# SFPextension.net
KiCad netlist of a schematic drawn in Altium Designer
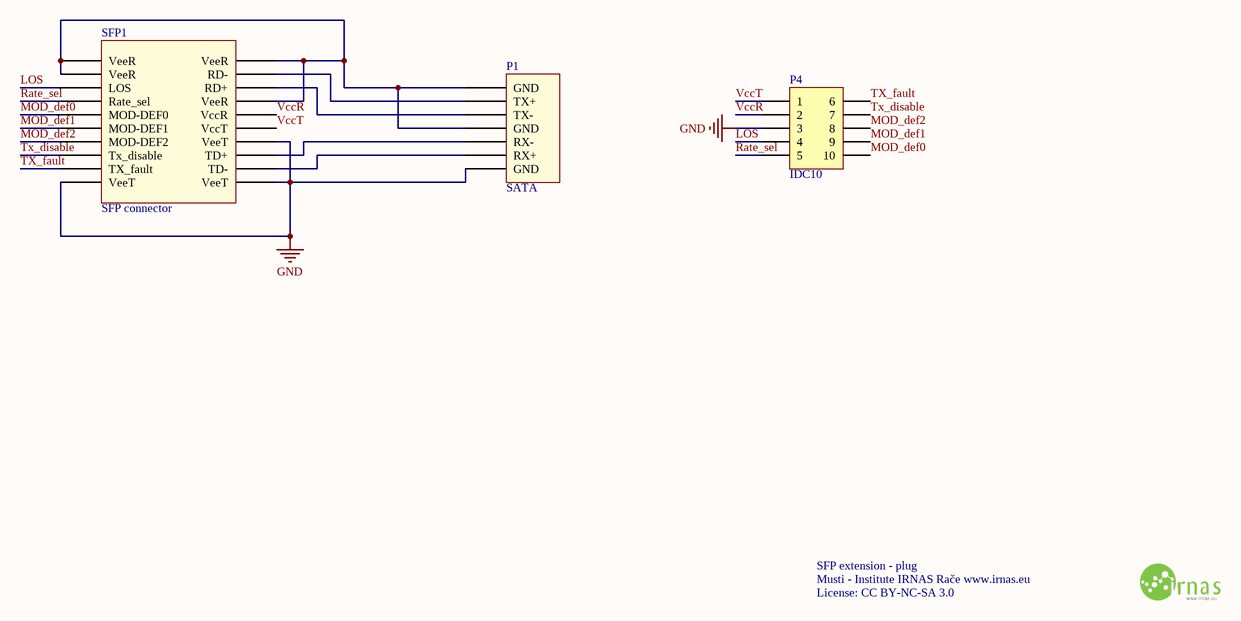
[diagram p0: SFPextension.SchDoc]

(export (version "E")
  (design (tool "Eeschema 10.0.6"))
  (components
    (comp (ref "P1")
      (value "SATA")
      (footprint "SATA pcb")
      (description "sata")
      (libsource (lib "GeneralComponents") (part "SATA"))
    )
    (comp (ref "P4")
      (value "IDC10")
      (footprint "HDR2X5_CEN")
      (description "Header, 5-Pin, Dual row")
      (fields (field (name "PUBLISHER") "Altium Limited"))
      (libsource (lib "Miscellaneous Connectors") (part "Header 5X2A"))
    )
    (comp (ref "SFP1")
      (value "SFP connector")
      (footprint "SFP pcb con")
      (libsource (lib "GeneralComponents") (part "SFP connector"))
    )
  )
  (nets
    (net (code "1") (name "/LOS") (class "Default")
      (node (ref "P4") (pin "4") (pinfunction "4_4") (pintype "passive"))
      (node (ref "SFP1") (pin "8") (pinfunction "LOS_8") (pintype "power_in"))
    )
    (net (code "2") (name "/MOD_def0") (class "Default")
      (node (ref "P4") (pin "10") (pinfunction "10_10") (pintype "passive"))
      (node (ref "SFP1") (pin "6") (pinfunction "MOD-DEF0_6") (pintype "power_in"))
    )
    (net (code "3") (name "/MOD_def1") (class "Default")
      (node (ref "P4") (pin "9") (pinfunction "9_9") (pintype "passive"))
      (node (ref "SFP1") (pin "5") (pinfunction "MOD-DEF1_5") (pintype "power_in"))
    )
    (net (code "4") (name "/MOD_def2") (class "Default")
      (node (ref "P4") (pin "8") (pinfunction "8_8") (pintype "passive"))
      (node (ref "SFP1") (pin "4") (pinfunction "MOD-DEF2_4") (pintype "power_in"))
    )
    (net (code "5") (name "/Rate_sel") (class "Default")
      (node (ref "P4") (pin "5") (pinfunction "5_5") (pintype "passive"))
      (node (ref "SFP1") (pin "7") (pinfunction "Rate_sel_7") (pintype "power_in"))
    )
    (net (code "6") (name "/TX_fault") (class "Default")
      (node (ref "P4") (pin "6") (pinfunction "6_6") (pintype "passive"))
      (node (ref "SFP1") (pin "2") (pinfunction "TX_fault_2") (pintype "power_in"))
    )
    (net (code "7") (name "/Tx_disable") (class "Default")
      (node (ref "P4") (pin "7") (pinfunction "7_7") (pintype "passive"))
      (node (ref "SFP1") (pin "3") (pinfunction "Tx_disable_3") (pintype "power_in"))
    )
    (net (code "8") (name "/VccR") (class "Default")
      (node (ref "P4") (pin "2") (pinfunction "2_2") (pintype "passive"))
      (node (ref "SFP1") (pin "15") (pinfunction "VccR_15") (pintype "power_in"))
    )
    (net (code "9") (name "/VccT") (class "Default")
      (node (ref "P4") (pin "1") (pinfunction "1_1") (pintype "passive"))
      (node (ref "SFP1") (pin "16") (pinfunction "VccT_16") (pintype "power_in"))
    )
    (net (code "10") (name "GND") (class "Default")
      (node (ref "P1") (pin "7") (pinfunction "GND_7") (pintype "power_in"))
      (node (ref "P4") (pin "3") (pinfunction "3_3") (pintype "passive"))
      (node (ref "SFP1") (pin "1") (pinfunction "VeeT_1") (pintype "power_in"))
      (node (ref "SFP1") (pin "17") (pinfunction "VeeT_17") (pintype "power_in"))
      (node (ref "SFP1") (pin "20") (pinfunction "VeeT_20") (pintype "power_in"))
    )
    (net (code "11") (name "Net-(P1-GND-Pad1)") (class "Default")
      (node (ref "P1") (pin "1") (pinfunction "GND_1") (pintype "power_in"))
      (node (ref "P1") (pin "4") (pinfunction "GND_4") (pintype "power_in"))
      (node (ref "SFP1") (pin "10") (pinfunction "VeeR_10") (pintype "power_in"))
      (node (ref "SFP1") (pin "11") (pinfunction "VeeR_11") (pintype "power_in"))
      (node (ref "SFP1") (pin "14") (pinfunction "VeeR_14") (pintype "power_in"))
      (node (ref "SFP1") (pin "9") (pinfunction "VeeR_9") (pintype "power_in"))
    )
    (net (code "12") (name "Net-(P1-RX+)") (class "Default")
      (node (ref "P1") (pin "6") (pinfunction "RX+_6") (pintype "power_in"))
      (node (ref "SFP1") (pin "19") (pinfunction "TD-_19") (pintype "power_in"))
    )
    (net (code "13") (name "Net-(P1-RX-)") (class "Default")
      (node (ref "P1") (pin "5") (pinfunction "RX-_5") (pintype "power_in"))
      (node (ref "SFP1") (pin "18") (pinfunction "TD+_18") (pintype "power_in"))
    )
    (net (code "14") (name "Net-(P1-TX+)") (class "Default")
      (node (ref "P1") (pin "2") (pinfunction "TX+_2") (pintype "power_in"))
      (node (ref "SFP1") (pin "12") (pinfunction "RD-_12") (pintype "power_in"))
    )
    (net (code "15") (name "Net-(P1-TX-)") (class "Default")
      (node (ref "P1") (pin "3") (pinfunction "TX-_3") (pintype "power_in"))
      (node (ref "SFP1") (pin "13") (pinfunction "RD+_13") (pintype "power_in"))
    )
  )
)
